# Core.net
KiCad netlist of a schematic drawn in Altium Designer
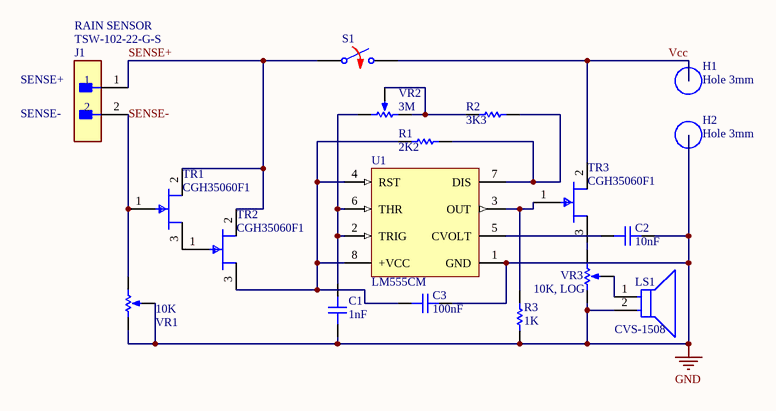
[diagram p0: Core.SchDoc]

(export (version "E")
  (design (tool "Eeschema 10.0.6"))
  (components
    (comp (ref "C1")
      (value "1nF")
      (footprint "CAP_0201")
      (description "Capacitor SMD 0201")
      (libsource (lib "Schematic-Lib-PhilsLab") (part "CAP_0201"))
    )
    (comp (ref "C2")
      (value "10nF")
      (footprint "CAP_0201")
      (description "Capacitor SMD 0201")
      (libsource (lib "Schematic-Lib-PhilsLab") (part "CAP_0201"))
    )
    (comp (ref "C3")
      (value "100nF")
      (footprint "CAP_0201")
      (description "Capacitor SMD 0201")
      (libsource (lib "Schematic-Lib-PhilsLab") (part "CAP_0201"))
    )
    (comp (ref "H1")
      (value "Hole 3mm")
      (footprint "Hole 3mm")
      (libsource (lib "ECE Lib 22") (part "Hole 3mm"))
    )
    (comp (ref "H2")
      (value "Hole 3mm")
      (footprint "Hole 3mm")
      (libsource (lib "ECE Lib 22") (part "Hole 3mm"))
    )
    (comp (ref "J1")
      (value "TSW-102-22-G-S")
      (footprint "FP-TSW-102-22-G-S-MFG")
      (description "CONN HEADER VERT 2POS 2.54MM")
      (libsource (lib "Altium Content Vault") (part "3bc925449376181038e59eaffc5286c"))
    )
    (comp (ref "LS1")
      (value "CVS-1508")
      (footprint "FP-CVS-1508-MFG")
      (description "SPEAKER 8OHM 300MW TOP PORT 87DB")
      (fields
        (field (name "MANUFACTURER") "CUI Inc")
        (field (name "OCTOPART") "https://octopart.com/cvs-1508-cui-21325683")
      )
      (libsource (lib "Altium Content Vault") (part "1973c4b650225fd2ddacaff6b763965"))
    )
    (comp (ref "R1")
      (value "2K2")
      (description "Resistor")
      (libsource (lib "Simulation Generic Components") (part "Resistor"))
    )
    (comp (ref "R2")
      (value "3K3")
      (description "Resistor")
      (libsource (lib "Simulation Generic Components") (part "Resistor"))
    )
    (comp (ref "R3")
      (value "1K")
      (description "Resistor")
      (libsource (lib "Simulation Generic Components") (part "Resistor"))
    )
    (comp (ref "S1")
      (value "Switch Normally Opened")
      (libsource (lib "Simulation Generic Components") (part "SW NO"))
    )
    (comp (ref "TR1")
      (value "CGH35060F1")
      (footprint "FP-440193-IPC_C")
      (description "RF Mosfet HEMT 28 V 250 mA 3.3-3.6GHz 11.5dB 60W 440193")
      (libsource (lib "Altium Content Vault") (part "034903fd4a779be59c9ee36cb9ea9b9"))
    )
    (comp (ref "TR2")
      (value "CGH35060F1")
      (footprint "FP-440193-IPC_C")
      (description "RF Mosfet HEMT 28 V 250 mA 3.3-3.6GHz 11.5dB 60W 440193")
      (libsource (lib "Altium Content Vault") (part "034903fd4a779be59c9ee36cb9ea9b9"))
    )
    (comp (ref "TR3")
      (value "CGH35060F1")
      (footprint "FP-440193-IPC_C")
      (description "RF Mosfet HEMT 28 V 250 mA 3.3-3.6GHz 11.5dB 60W 440193")
      (libsource (lib "Altium Content Vault") (part "034903fd4a779be59c9ee36cb9ea9b9"))
    )
    (comp (ref "U1")
      (value "LM555CM")
      (footprint "D0008A_L")
      (description "Timer, 8-pin Narrow SOIC")
      (fields (field (name "MANUFACTURER") "Texas Instruments"))
      (libsource (lib "Altium Content Vault") (part "AN-TIMER-LM555-8"))
    )
    (comp (ref "VR1")
      (value "10K")
      (footprint "CT2260-ND")
      (description "Potentiometer")
      (fields (field (name "Comment") "RPot_7") (field (name "PUBLISHER") "Altium Limited"))
      (libsource (lib "ECE Lib 22") (part "RPot_4"))
    )
    (comp (ref "VR2")
      (value "3M")
      (footprint "CT2260-ND")
      (description "Potentiometer")
      (fields (field (name "Comment") "RPot_7") (field (name "PUBLISHER") "Altium Limited"))
      (libsource (lib "ECE Lib 22") (part "RPot_4"))
    )
    (comp (ref "VR3")
      (value "10K, LOG")
      (footprint "CT2260-ND")
      (description "Potentiometer")
      (fields (field (name "Comment") "RPot_7") (field (name "PUBLISHER") "Altium Limited"))
      (libsource (lib "ECE Lib 22") (part "RPot_4"))
    )
  )
  (nets
    (net (code "1") (name "/SENSE+") (class "Default")
      (node (ref "J1") (pin "1") (pinfunction "1_1") (pintype "passive"))
      (node (ref "S1") (pin "1") (pinfunction "1_1") (pintype "passive"))
      (node (ref "TR1") (pin "2") (pinfunction "DRAIN_2") (pintype "passive"))
      (node (ref "TR2") (pin "2") (pinfunction "DRAIN_2") (pintype "passive"))
    )
    (net (code "2") (name "/SENSE-") (class "Default")
      (node (ref "J1") (pin "2") (pinfunction "2_2") (pintype "passive"))
      (node (ref "TR1") (pin "1") (pinfunction "GATE_1") (pintype "passive"))
      (node (ref "VR1") (pin "3") (pinfunction "BOT_3") (pintype "passive"))
    )
    (net (code "3") (name "/Vcc") (class "Default")
      (node (ref "S1") (pin "2") (pinfunction "2_2") (pintype "passive"))
      (node (ref "TR3") (pin "2") (pinfunction "DRAIN_2") (pintype "passive"))
    )
    (net (code "4") (name "GND") (class "Default")
      (node (ref "C1") (pin "1") (pinfunction "1_1") (pintype "passive"))
      (node (ref "C2") (pin "2") (pinfunction "2_2") (pintype "passive"))
      (node (ref "C3") (pin "2") (pinfunction "2_2") (pintype "passive"))
      (node (ref "LS1") (pin "2") (pinfunction "A_2") (pintype "passive"))
      (node (ref "R3") (pin "2") (pinfunction "2_2") (pintype "passive"))
      (node (ref "U1") (pin "1") (pinfunction "GND_1") (pintype "power_in"))
      (node (ref "VR1") (pin "1") (pinfunction "TOP_1") (pintype "passive"))
      (node (ref "VR1") (pin "2") (pinfunction "TAP_2") (pintype "passive"))
      (node (ref "VR3") (pin "1") (pinfunction "TOP_1") (pintype "passive"))
    )
    (net (code "5") (name "Net-(LS1-C)") (class "Default")
      (node (ref "LS1") (pin "1") (pinfunction "C_1") (pintype "passive"))
      (node (ref "VR3") (pin "2") (pinfunction "TAP_2") (pintype "passive"))
    )
    (net (code "6") (name "Net-(TR1-SOURCE)") (class "Default")
      (node (ref "TR1") (pin "3") (pinfunction "SOURCE_3") (pintype "passive"))
      (node (ref "TR2") (pin "1") (pinfunction "GATE_1") (pintype "passive"))
    )
    (net (code "7") (name "Net-(TR2-SOURCE)") (class "Default")
      (node (ref "C3") (pin "1") (pinfunction "1_1") (pintype "passive"))
      (node (ref "R1") (pin "1") (pinfunction "1_1") (pintype "passive"))
      (node (ref "TR2") (pin "3") (pinfunction "SOURCE_3") (pintype "passive"))
      (node (ref "U1") (pin "4") (pinfunction "RST_4") (pintype "input"))
      (node (ref "U1") (pin "8") (pinfunction "+VCC_8") (pintype "power_in"))
    )
    (net (code "8") (name "Net-(TR3-GATE)") (class "Default")
      (node (ref "R3") (pin "1") (pinfunction "1_1") (pintype "passive"))
      (node (ref "TR3") (pin "1") (pinfunction "GATE_1") (pintype "passive"))
      (node (ref "U1") (pin "3") (pinfunction "OUT_3") (pintype "output"))
    )
    (net (code "9") (name "Net-(TR3-SOURCE)") (class "Default")
      (node (ref "TR3") (pin "3") (pinfunction "SOURCE_3") (pintype "passive"))
      (node (ref "VR3") (pin "3") (pinfunction "BOT_3") (pintype "passive"))
    )
    (net (code "10") (name "Net-(U1-CVOLT)") (class "Default")
      (node (ref "C2") (pin "1") (pinfunction "1_1") (pintype "passive"))
      (node (ref "U1") (pin "5") (pinfunction "CVOLT_5") (pintype "passive"))
    )
    (net (code "11") (name "Net-(U1-DIS)") (class "Default")
      (node (ref "R1") (pin "2") (pinfunction "2_2") (pintype "passive"))
      (node (ref "R2") (pin "2") (pinfunction "2_2") (pintype "passive"))
      (node (ref "U1") (pin "7") (pinfunction "DIS_7") (pintype "open_collector"))
    )
    (net (code "12") (name "Net-(U1-THR)") (class "Default")
      (node (ref "C1") (pin "2") (pinfunction "2_2") (pintype "passive"))
      (node (ref "U1") (pin "2") (pinfunction "TRIG_2") (pintype "input"))
      (node (ref "U1") (pin "6") (pinfunction "THR_6") (pintype "input"))
      (node (ref "VR2") (pin "3") (pinfunction "BOT_3") (pintype "passive"))
    )
    (net (code "13") (name "Net-(VR2-TAP)") (class "Default")
      (node (ref "R2") (pin "1") (pinfunction "1_1") (pintype "passive"))
      (node (ref "VR2") (pin "1") (pinfunction "TOP_1") (pintype "passive"))
      (node (ref "VR2") (pin "2") (pinfunction "TAP_2") (pintype "passive"))
    )
  )
)
